# mix_rxd.net
KiCad netlist of a schematic drawn in Altium Designer
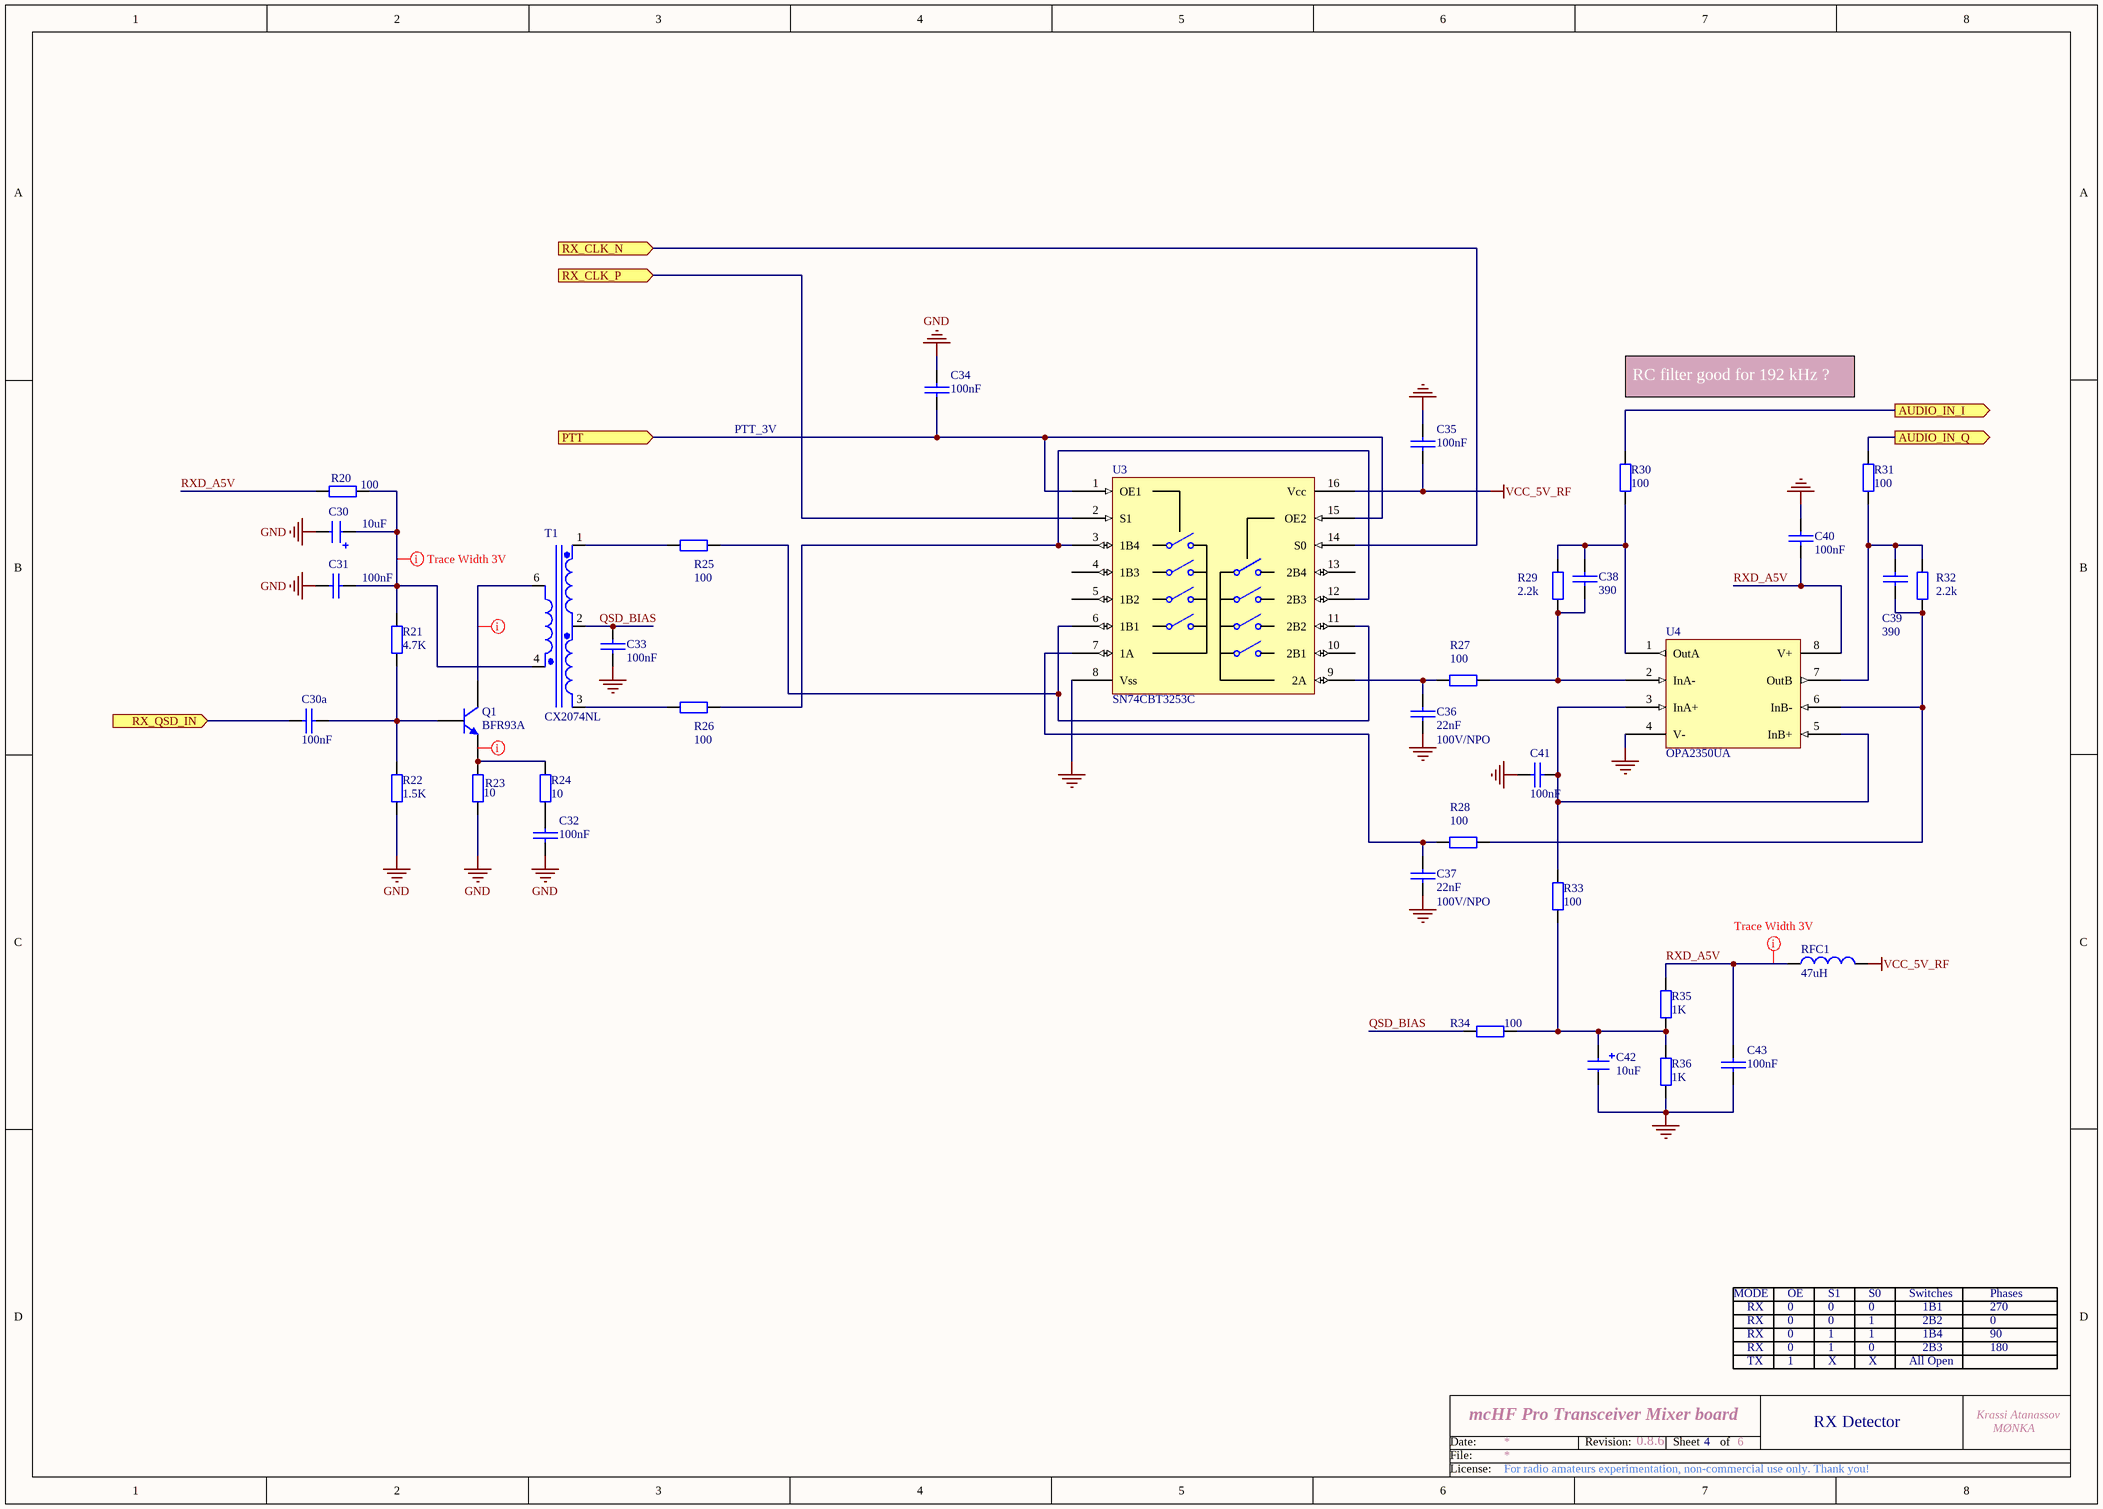
[diagram p0: mix_rxd.SchDoc]

(export (version "E")
  (design (tool "Eeschema 10.0.6"))
  (components
    (comp (ref "C30")
      (value "10uF")
      (footprint "1206_Elec_Cap")
      (description "Electrolitic capacitor")
      (libsource (lib "mcHF_rf") (part "CAP-POL"))
    )
    (comp (ref "C30a")
      (value "100nF")
      (footprint "0805")
      (description "Capacitor")
      (libsource (lib "mcHF_rf") (part "CAP"))
    )
    (comp (ref "C31")
      (value "100nF")
      (footprint "0805")
      (description "Capacitor")
      (libsource (lib "mcHF_rf") (part "CAP"))
    )
    (comp (ref "C32")
      (value "100nF")
      (footprint "0805")
      (description "Capacitor")
      (libsource (lib "mcHF_rf") (part "CAP"))
    )
    (comp (ref "C33")
      (value "100nF")
      (footprint "0805")
      (description "Capacitor")
      (libsource (lib "mcHF_rf") (part "CAP"))
    )
    (comp (ref "C34")
      (value "100nF")
      (footprint "0805")
      (description "Capacitor")
      (libsource (lib "mcHF_rf") (part "CAP"))
    )
    (comp (ref "C35")
      (value "100nF")
      (footprint "0805")
      (description "Capacitor")
      (libsource (lib "mcHF_rf") (part "CAP"))
    )
    (comp (ref "C36")
      (value "22nF")
      (footprint "CAP_B")
      (description "Capacitor")
      (fields (field (name "VOLTAGE") "100V/NPO"))
      (libsource (lib "mcHF_rf") (part "CAP"))
    )
    (comp (ref "C37")
      (value "22nF")
      (footprint "CAP_B")
      (description "Capacitor")
      (fields (field (name "VOLTAGE") "100V/NPO"))
      (libsource (lib "mcHF_rf") (part "CAP"))
    )
    (comp (ref "C38")
      (value "390")
      (footprint "0805")
      (description "Capacitor")
      (libsource (lib "mcHF_rf") (part "CAP"))
    )
    (comp (ref "C39")
      (value "390")
      (footprint "0805")
      (description "Capacitor")
      (libsource (lib "mcHF_rf") (part "CAP"))
    )
    (comp (ref "C40")
      (value "100nF")
      (footprint "0805")
      (description "Capacitor")
      (libsource (lib "mcHF_rf") (part "CAP"))
    )
    (comp (ref "C41")
      (value "100nF")
      (footprint "0805")
      (description "Capacitor")
      (libsource (lib "mcHF_rf") (part "CAP"))
    )
    (comp (ref "C42")
      (value "10uF")
      (footprint "1206_Elec_Cap")
      (description "Electrolitic capacitor")
      (libsource (lib "mcHF_rf") (part "CAP-POL"))
    )
    (comp (ref "C43")
      (value "100nF")
      (footprint "0805")
      (description "Capacitor")
      (libsource (lib "mcHF_rf") (part "CAP"))
    )
    (comp (ref "Q1")
      (value "BFR93A")
      (footprint "SOT-23")
      (description "TRANSISTOR, RF, NPN, 12V, 0.035MA,SOT-23")
      (libsource (lib "mcHF_rf") (part "BFR93A"))
    )
    (comp (ref "R20")
      (value "100")
      (footprint "0805")
      (description "Resistor")
      (libsource (lib "") (part "RES_1"))
    )
    (comp (ref "R21")
      (value "4.7K")
      (footprint "0805")
      (description "Resistor")
      (libsource (lib "") (part "RES_3"))
    )
    (comp (ref "R22")
      (value "1.5K")
      (footprint "0805")
      (description "Resistor")
      (libsource (lib "") (part "RES_3"))
    )
    (comp (ref "R23")
      (value "10")
      (footprint "0805")
      (description "Resistor")
      (libsource (lib "mcHF_rf") (part "RES"))
    )
    (comp (ref "R24")
      (value "10")
      (footprint "0805")
      (description "Resistor")
      (libsource (lib "mcHF_rf") (part "RES"))
    )
    (comp (ref "R25")
      (value "100")
      (footprint "0805")
      (description "Resistor")
      (libsource (lib "") (part "RES_1"))
    )
    (comp (ref "R26")
      (value "100")
      (footprint "0805")
      (description "Resistor")
      (libsource (lib "") (part "RES_1"))
    )
    (comp (ref "R27")
      (value "100")
      (footprint "0805")
      (description "Resistor")
      (libsource (lib "") (part "RES_1"))
    )
    (comp (ref "R28")
      (value "100")
      (footprint "0805")
      (description "Resistor")
      (libsource (lib "") (part "RES_1"))
    )
    (comp (ref "R29")
      (value "2.2k")
      (footprint "0805")
      (description "Resistor")
      (libsource (lib "mcHF_rf") (part "RES"))
    )
    (comp (ref "R30")
      (value "100")
      (footprint "0805")
      (description "Resistor")
      (libsource (lib "mcHF_rf") (part "RES"))
    )
    (comp (ref "R31")
      (value "100")
      (footprint "0805")
      (description "Resistor")
      (libsource (lib "mcHF_rf") (part "RES"))
    )
    (comp (ref "R32")
      (value "2.2k")
      (footprint "0805")
      (description "Resistor")
      (libsource (lib "mcHF_rf") (part "RES"))
    )
    (comp (ref "R33")
      (value "100")
      (footprint "0805")
      (description "Resistor")
      (libsource (lib "mcHF_rf") (part "RES"))
    )
    (comp (ref "R34")
      (value "100")
      (footprint "0805")
      (description "Resistor")
      (libsource (lib "") (part "RES_2"))
    )
    (comp (ref "R35")
      (value "1K")
      (footprint "0805")
      (description "Resistor")
      (libsource (lib "mcHF_rf") (part "RES"))
    )
    (comp (ref "R36")
      (value "1K")
      (footprint "0805")
      (description "Resistor")
      (libsource (lib "mcHF_rf") (part "RES"))
    )
    (comp (ref "RFC1")
      (value "47uH")
      (footprint "0805")
      (description "INDUCTOR, SIGNAL LINE, 4.7UH, 1005")
      (libsource (lib "mcHF_rf") (part "TDK-NLV25T"))
    )
    (comp (ref "T1")
      (value "CX2074NL")
      (footprint "SOP5_NEW1")
      (description "Wideband RF Transformer 1:4")
      (libsource (lib "mcHF_rf") (part "CX2074NL"))
    )
    (comp (ref "U3")
      (value "SN74CBT3253C")
      (footprint "SO-16-Pro")
      (description "Dual 4:1 Demux/Analog Switch")
      (libsource (lib "mcHF_rf") (part "SN74CBT3253C"))
    )
    (comp (ref "U4")
      (value "OPA2350UA")
      (footprint "SO-8")
      (description "High Speed, Single Supply OpAmp")
      (libsource (lib "mcHF_rf") (part "OPA2350UA"))
    )
  )
  (nets
    (net (code "1") (name "/AUDIO_IN_I") (class "Default")
      (node (ref "R30") (pin "2") (pinfunction "2_2") (pintype "passive"))
    )
    (net (code "2") (name "/AUDIO_IN_Q") (class "Default")
      (node (ref "R31") (pin "2") (pinfunction "2_2") (pintype "passive"))
    )
    (net (code "3") (name "/PTT") (class "Default")
      (node (ref "C34") (pin "1") (pinfunction "1_1") (pintype "passive"))
      (node (ref "U3") (pin "1") (pinfunction "OE1_1") (pintype "input"))
      (node (ref "U3") (pin "15") (pinfunction "OE2_15") (pintype "input"))
    )
    (net (code "4") (name "/QSD_BIAS") (class "Default")
      (node (ref "C33") (pin "1") (pinfunction "1_1") (pintype "passive"))
      (node (ref "R34") (pin "2") (pinfunction "2_2") (pintype "passive"))
      (node (ref "T1") (pin "2") (pinfunction "SecCmn_2") (pintype "passive"))
    )
    (net (code "5") (name "/RXD_A5V") (class "Default")
      (node (ref "C40") (pin "2") (pinfunction "2_2") (pintype "passive"))
      (node (ref "C43") (pin "2") (pinfunction "2_2") (pintype "passive"))
      (node (ref "R20") (pin "1") (pinfunction "1_1") (pintype "passive"))
      (node (ref "R35") (pin "2") (pinfunction "2_2") (pintype "passive"))
      (node (ref "RFC1") (pin "1") (pinfunction "1_1") (pintype "passive"))
      (node (ref "U4") (pin "8") (pinfunction "V+_8") (pintype "power_in"))
    )
    (net (code "6") (name "/RX_CLK_N") (class "Default")
      (node (ref "U3") (pin "14") (pinfunction "S0_14") (pintype "input"))
    )
    (net (code "7") (name "/RX_CLK_P") (class "Default")
      (node (ref "U3") (pin "2") (pinfunction "S1_2") (pintype "input"))
    )
    (net (code "8") (name "/RX_QSD_IN") (class "Default")
      (node (ref "C30a") (pin "1") (pinfunction "1_1") (pintype "passive"))
    )
    (net (code "9") (name "GND") (class "Default")
      (node (ref "C30") (pin "2") (pinfunction "2_2") (pintype "passive"))
      (node (ref "C31") (pin "2") (pinfunction "2_2") (pintype "passive"))
      (node (ref "C32") (pin "1") (pinfunction "1_1") (pintype "passive"))
      (node (ref "C33") (pin "2") (pinfunction "2_2") (pintype "passive"))
      (node (ref "C34") (pin "2") (pinfunction "2_2") (pintype "passive"))
      (node (ref "C35") (pin "2") (pinfunction "2_2") (pintype "passive"))
      (node (ref "C36") (pin "2") (pinfunction "2_2") (pintype "passive"))
      (node (ref "C37") (pin "2") (pinfunction "2_2") (pintype "passive"))
      (node (ref "C40") (pin "1") (pinfunction "1_1") (pintype "passive"))
      (node (ref "C41") (pin "2") (pinfunction "2_2") (pintype "passive"))
      (node (ref "C42") (pin "2") (pinfunction "2_2") (pintype "passive"))
      (node (ref "C43") (pin "1") (pinfunction "1_1") (pintype "passive"))
      (node (ref "R22") (pin "2") (pinfunction "2_2") (pintype "passive"))
      (node (ref "R23") (pin "1") (pinfunction "1_1") (pintype "passive"))
      (node (ref "R36") (pin "1") (pinfunction "1_1") (pintype "passive"))
      (node (ref "U3") (pin "8") (pinfunction "Vss_8") (pintype "power_in"))
      (node (ref "U4") (pin "4") (pinfunction "V-_4") (pintype "power_in"))
    )
    (net (code "10") (name "Net-(C32-Pad2)") (class "Default")
      (node (ref "C32") (pin "2") (pinfunction "2_2") (pintype "passive"))
      (node (ref "R24") (pin "1") (pinfunction "1_1") (pintype "passive"))
    )
    (net (code "11") (name "Net-(C42-Pad1)") (class "Default")
      (node (ref "C42") (pin "1") (pinfunction "1_1") (pintype "passive"))
      (node (ref "R33") (pin "1") (pinfunction "1_1") (pintype "passive"))
      (node (ref "R34") (pin "1") (pinfunction "1_1") (pintype "passive"))
      (node (ref "R35") (pin "1") (pinfunction "1_1") (pintype "passive"))
      (node (ref "R36") (pin "2") (pinfunction "2_2") (pintype "passive"))
    )
    (net (code "12") (name "Net-(Q1-B)") (class "Default")
      (node (ref "C30a") (pin "2") (pinfunction "2_2") (pintype "passive"))
      (node (ref "Q1") (pin "1") (pinfunction "B_1") (pintype "passive"))
      (node (ref "R21") (pin "2") (pinfunction "2_2") (pintype "passive"))
      (node (ref "R22") (pin "1") (pinfunction "1_1") (pintype "passive"))
    )
    (net (code "13") (name "Net-(Q1-C)") (class "Default")
      (node (ref "Q1") (pin "3") (pinfunction "C_3") (pintype "passive"))
      (node (ref "T1") (pin "6") (pinfunction "Pri+_6") (pintype "passive"))
    )
    (net (code "14") (name "Net-(Q1-E)") (class "Default")
      (node (ref "Q1") (pin "2") (pinfunction "E_2") (pintype "passive"))
      (node (ref "R23") (pin "2") (pinfunction "2_2") (pintype "passive"))
      (node (ref "R24") (pin "2") (pinfunction "2_2") (pintype "passive"))
    )
    (net (code "15") (name "Net-(T1-Pri-)") (class "Default")
      (node (ref "C30") (pin "1") (pinfunction "1_1") (pintype "passive"))
      (node (ref "C31") (pin "1") (pinfunction "1_1") (pintype "passive"))
      (node (ref "R20") (pin "2") (pinfunction "2_2") (pintype "passive"))
      (node (ref "R21") (pin "1") (pinfunction "1_1") (pintype "passive"))
      (node (ref "T1") (pin "4") (pinfunction "Pri-_4") (pintype "passive"))
    )
    (net (code "16") (name "Net-(T1-Sec0)") (class "Default")
      (node (ref "R25") (pin "1") (pinfunction "1_1") (pintype "passive"))
      (node (ref "T1") (pin "1") (pinfunction "Sec0_1") (pintype "passive"))
    )
    (net (code "17") (name "Net-(T1-Sec180)") (class "Default")
      (node (ref "R26") (pin "1") (pinfunction "1_1") (pintype "passive"))
      (node (ref "T1") (pin "3") (pinfunction "Sec180_3") (pintype "passive"))
    )
    (net (code "18") (name "Net-(U3-1A)") (class "Default")
      (node (ref "C37") (pin "1") (pinfunction "1_1") (pintype "passive"))
      (node (ref "R28") (pin "1") (pinfunction "1_1") (pintype "passive"))
      (node (ref "U3") (pin "7") (pinfunction "1A_7") (pintype "bidirectional"))
    )
    (net (code "19") (name "Net-(U3-1B1)") (class "Default")
      (node (ref "R25") (pin "2") (pinfunction "2_2") (pintype "passive"))
      (node (ref "U3") (pin "11") (pinfunction "2B2_11") (pintype "bidirectional"))
      (node (ref "U3") (pin "6") (pinfunction "1B1_6") (pintype "bidirectional"))
    )
    (net (code "20") (name "Net-(U3-1B4)") (class "Default")
      (node (ref "R26") (pin "2") (pinfunction "2_2") (pintype "passive"))
      (node (ref "U3") (pin "12") (pinfunction "2B3_12") (pintype "bidirectional"))
      (node (ref "U3") (pin "3") (pinfunction "1B4_3") (pintype "bidirectional"))
    )
    (net (code "21") (name "Net-(U3-2A)") (class "Default")
      (node (ref "C36") (pin "1") (pinfunction "1_1") (pintype "passive"))
      (node (ref "R27") (pin "1") (pinfunction "1_1") (pintype "passive"))
      (node (ref "U3") (pin "9") (pinfunction "2A_9") (pintype "bidirectional"))
    )
    (net (code "22") (name "Net-(U4-InA+)") (class "Default")
      (node (ref "C41") (pin "1") (pinfunction "1_1") (pintype "passive"))
      (node (ref "R33") (pin "2") (pinfunction "2_2") (pintype "passive"))
      (node (ref "U4") (pin "3") (pinfunction "InA+_3") (pintype "input"))
      (node (ref "U4") (pin "5") (pinfunction "InB+_5") (pintype "input"))
    )
    (net (code "23") (name "Net-(U4-InA-)") (class "Default")
      (node (ref "C38") (pin "1") (pinfunction "1_1") (pintype "passive"))
      (node (ref "R27") (pin "2") (pinfunction "2_2") (pintype "passive"))
      (node (ref "R29") (pin "1") (pinfunction "1_1") (pintype "passive"))
      (node (ref "U4") (pin "2") (pinfunction "InA-_2") (pintype "input"))
    )
    (net (code "24") (name "Net-(U4-InB-)") (class "Default")
      (node (ref "C39") (pin "1") (pinfunction "1_1") (pintype "passive"))
      (node (ref "R28") (pin "2") (pinfunction "2_2") (pintype "passive"))
      (node (ref "R32") (pin "1") (pinfunction "1_1") (pintype "passive"))
      (node (ref "U4") (pin "6") (pinfunction "InB-_6") (pintype "input"))
    )
    (net (code "25") (name "Net-(U4-OutA)") (class "Default")
      (node (ref "C38") (pin "2") (pinfunction "2_2") (pintype "passive"))
      (node (ref "R29") (pin "2") (pinfunction "2_2") (pintype "passive"))
      (node (ref "R30") (pin "1") (pinfunction "1_1") (pintype "passive"))
      (node (ref "U4") (pin "1") (pinfunction "OutA_1") (pintype "output"))
    )
    (net (code "26") (name "Net-(U4-OutB)") (class "Default")
      (node (ref "C39") (pin "2") (pinfunction "2_2") (pintype "passive"))
      (node (ref "R31") (pin "1") (pinfunction "1_1") (pintype "passive"))
      (node (ref "R32") (pin "2") (pinfunction "2_2") (pintype "passive"))
      (node (ref "U4") (pin "7") (pinfunction "OutB_7") (pintype "output"))
    )
    (net (code "27") (name "VCC_5V_RF") (class "Default")
      (node (ref "C35") (pin "1") (pinfunction "1_1") (pintype "passive"))
      (node (ref "RFC1") (pin "2") (pinfunction "2_2") (pintype "passive"))
      (node (ref "U3") (pin "16") (pinfunction "Vcc_16") (pintype "power_in"))
    )
    (net (code "28") (name "unconnected-(U3-1B2-Pad5)") (class "Default")
      (node (ref "U3") (pin "5") (pinfunction "1B2_5") (pintype "bidirectional"))
    )
    (net (code "29") (name "unconnected-(U3-1B3-Pad4)") (class "Default")
      (node (ref "U3") (pin "4") (pinfunction "1B3_4") (pintype "bidirectional"))
    )
    (net (code "30") (name "unconnected-(U3-2B1-Pad10)") (class "Default")
      (node (ref "U3") (pin "10") (pinfunction "2B1_10") (pintype "bidirectional"))
    )
    (net (code "31") (name "unconnected-(U3-2B4-Pad13)") (class "Default")
      (node (ref "U3") (pin "13") (pinfunction "2B4_13") (pintype "bidirectional"))
    )
  )
)
